# ventilator_circuit.net
KiCad netlist of a schematic drawn in EAGLE
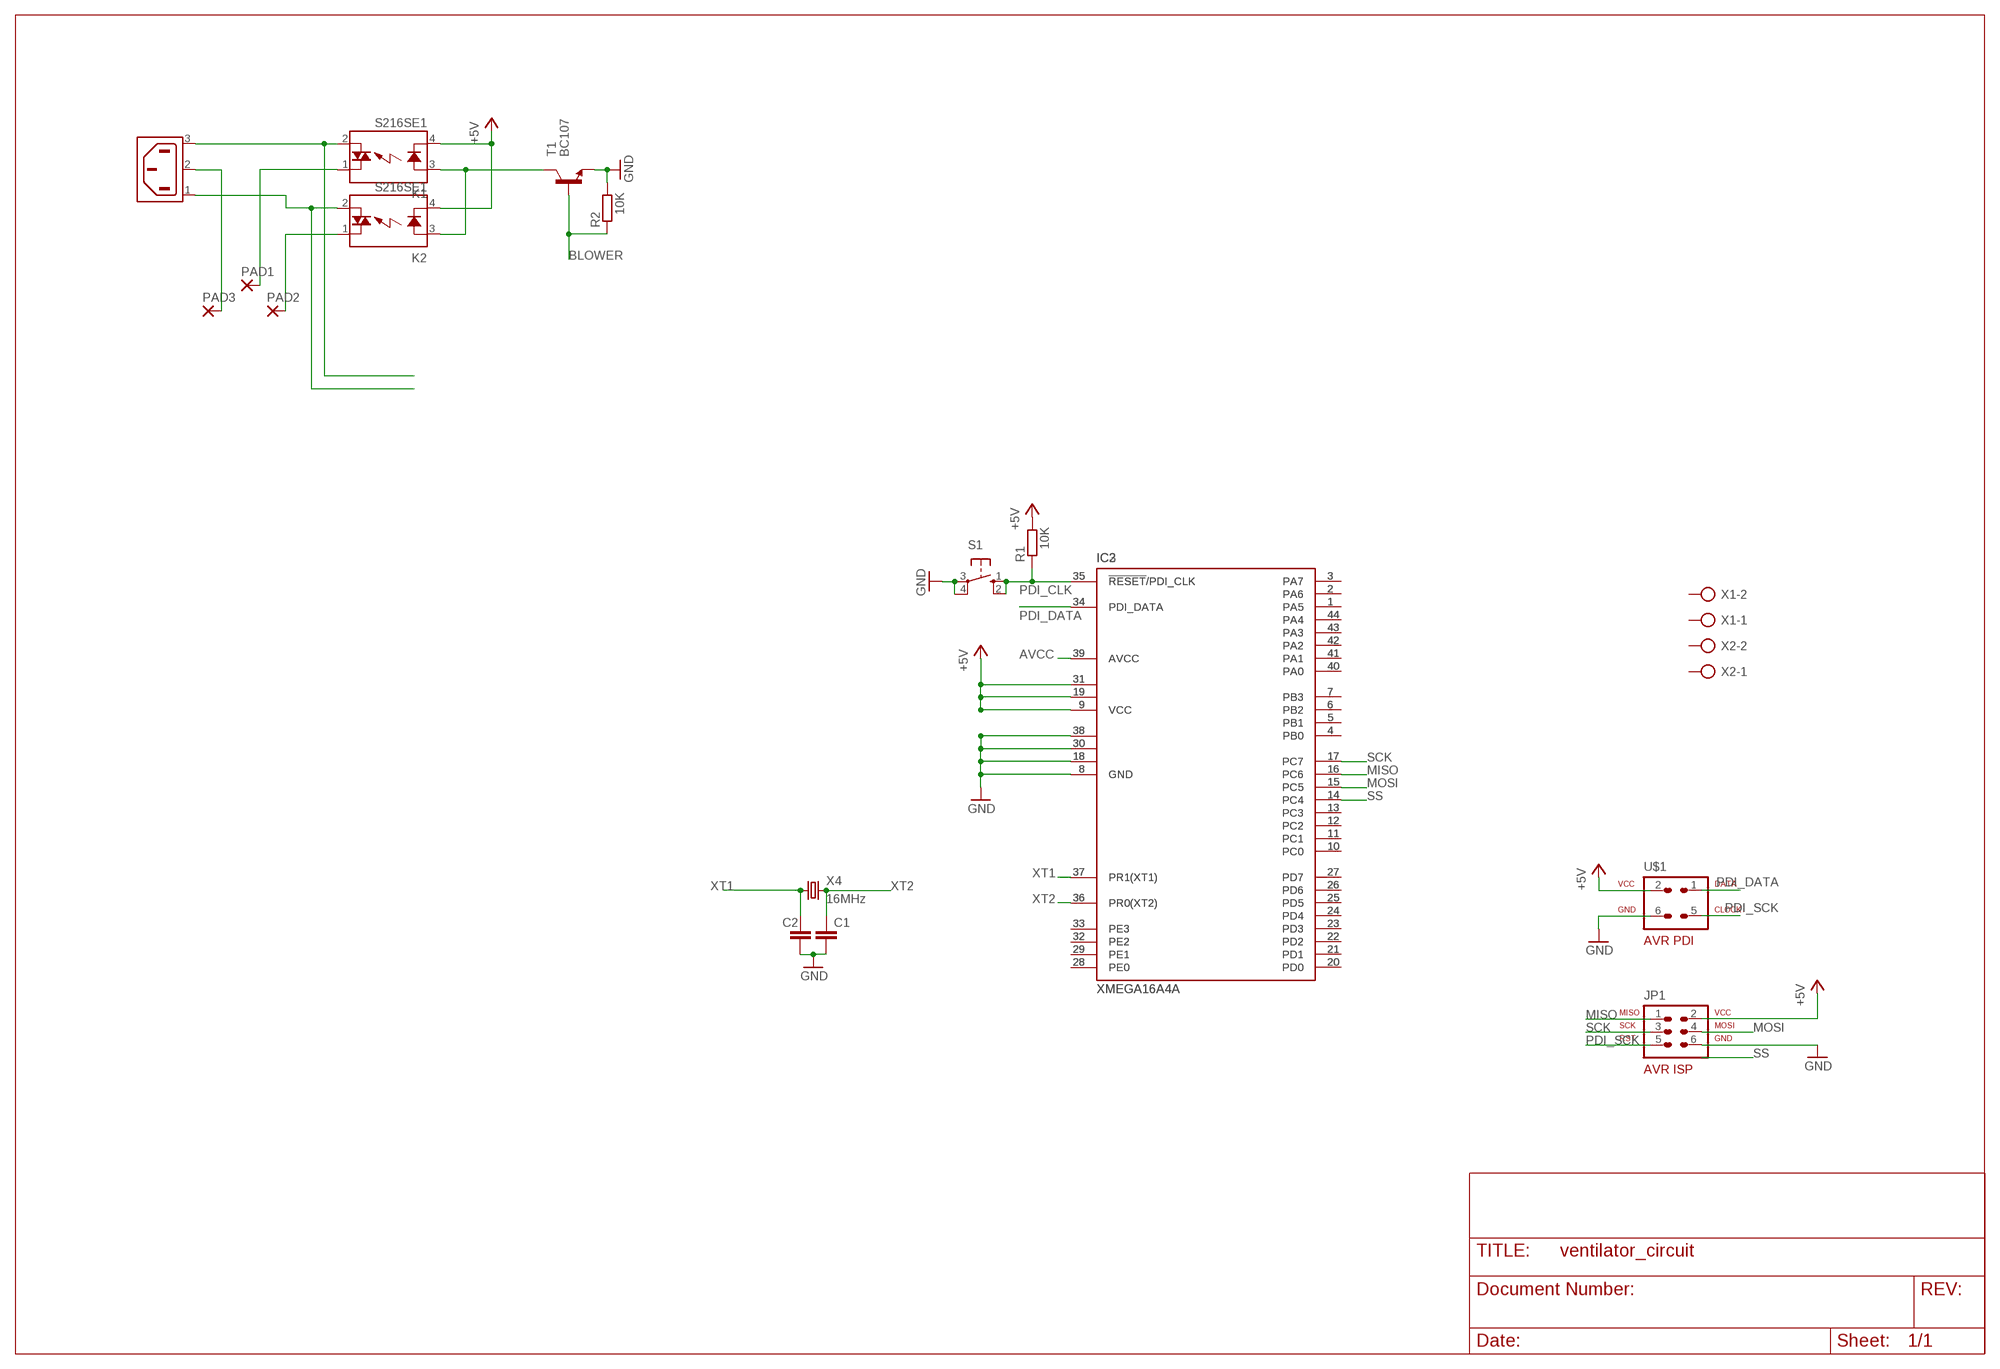
[diagram p0: schematic, sheet 1]

(export (version "E")
  (design (tool "Eeschema 10.0.6"))
  (components
    (comp (ref "C1")
      (value "C-EU025-025X050")
      (footprint "eagle-import:C025-025X050")
      (libsource (lib "eagle-import") (part "C-EU025-025X050"))
    )
    (comp (ref "C2")
      (value "C-EU025-025X050")
      (footprint "eagle-import:C025-025X050")
      (libsource (lib "eagle-import") (part "C-EU025-025X050"))
    )
    (comp (ref "IC2")
      (value "XMEGA16A4A")
      (footprint "eagle-import:TQFP44")
      (libsource (lib "eagle-import") (part "XMEGA16A4A"))
    )
    (comp (ref "IC3")
      (value "XMEGA16A4A")
      (footprint "eagle-import:TQFP44")
      (libsource (lib "eagle-import") (part "XMEGA16A4A"))
    )
    (comp (ref "JP1")
      (value "AVR-ISP-6VERT")
      (footprint "eagle-import:AVR-ISP-6")
      (libsource (lib "eagle-import") (part "AVR-ISP-6VERT"))
    )
    (comp (ref "K1")
      (value "S216SE1")
      (footprint "eagle-import:S2XXEX")
      (libsource (lib "eagle-import") (part "S216SE1"))
    )
    (comp (ref "K2")
      (value "S216SE1")
      (footprint "eagle-import:S2XXEX")
      (libsource (lib "eagle-import") (part "S216SE1"))
    )
    (comp (ref "PAD1")
      (value "3,81/1,4")
      (footprint "eagle-import:3,81_1,4")
      (libsource (lib "eagle-import") (part "3,81/1,4"))
    )
    (comp (ref "PAD2")
      (value "3,81/1,4")
      (footprint "eagle-import:3,81_1,4")
      (libsource (lib "eagle-import") (part "3,81/1,4"))
    )
    (comp (ref "PAD3")
      (value "3,81/1,4")
      (footprint "eagle-import:3,81_1,4")
      (libsource (lib "eagle-import") (part "3,81/1,4"))
    )
    (comp (ref "R1")
      (value "10K")
      (footprint "eagle-import:R0805")
      (libsource (lib "eagle-import") (part "R-EU_R0805"))
    )
    (comp (ref "R2")
      (value "10K")
      (footprint "eagle-import:R0805")
      (libsource (lib "eagle-import") (part "R-EU_R0805"))
    )
    (comp (ref "S1")
      (value "10-XX")
      (footprint "eagle-import:B3F-10XX")
      (fields (field (name "MPN") "B3F-1000"))
      (libsource (lib "eagle-import") (part "10-XX"))
    )
    (comp (ref "T1")
      (value "BC107")
      (footprint "eagle-import:TO18")
      (libsource (lib "eagle-import") (part "BC107"))
    )
    (comp (ref "U$1")
      (value "AVR-PDIVERT")
      (footprint "eagle-import:AVR-ISP-6")
      (libsource (lib "eagle-import") (part "AVR-PDIVERT"))
    )
    (comp (ref "X1")
      (value "AK500/2")
      (footprint "eagle-import:AK500_2")
      (libsource (lib "eagle-import") (part "AK500/2"))
    )
    (comp (ref "X2")
      (value "AK500/2")
      (footprint "eagle-import:AK500_2")
      (libsource (lib "eagle-import") (part "AK500/2"))
    )
    (comp (ref "X3")
      (value "6ESRM-P")
      (footprint "eagle-import:6ESRM-P")
      (fields (field (name "MF") "TYCO ELECTRONICS"))
      (libsource (lib "eagle-import") (part "6ESRM-P"))
    )
    (comp (ref "X4")
      (value "16MHz")
      (footprint "eagle-import:HC49")
      (libsource (lib "eagle-import") (part "CRYSTALS-NOGND-HC49/4H"))
    )
  )
  (nets
    (net (code "1") (name "+5V") (class "Default")
      (node (ref "IC2") (pin "19") (pinfunction "VCC1_19") (pintype "power_in"))
      (node (ref "IC2") (pin "31") (pinfunction "VCC2_31") (pintype "power_in"))
      (node (ref "IC2") (pin "9") (pinfunction "VCC_9") (pintype "power_in"))
      (node (ref "IC3") (pin "19") (pinfunction "VCC1_19") (pintype "power_in"))
      (node (ref "IC3") (pin "31") (pinfunction "VCC2_31") (pintype "power_in"))
      (node (ref "IC3") (pin "9") (pinfunction "VCC_9") (pintype "power_in"))
      (node (ref "JP1") (pin "2") (pinfunction "2_2") (pintype "passive"))
      (node (ref "K1") (pin "4") (pinfunction "K_4") (pintype "passive"))
      (node (ref "K2") (pin "4") (pinfunction "K_4") (pintype "passive"))
      (node (ref "R1") (pin "2") (pinfunction "2_2") (pintype "passive"))
      (node (ref "U$1") (pin "2") (pinfunction "2_2") (pintype "passive"))
    )
    (net (code "2") (name "/AVCC") (class "Default")
      (node (ref "IC2") (pin "39") (pinfunction "AVCC_39") (pintype "power_in"))
      (node (ref "IC3") (pin "39") (pinfunction "AVCC_39") (pintype "power_in"))
    )
    (net (code "3") (name "/BLOWER") (class "Default")
      (node (ref "R2") (pin "1") (pinfunction "1_1") (pintype "passive"))
      (node (ref "T1") (pin "2") (pinfunction "B_2") (pintype "passive"))
    )
    (net (code "4") (name "/MISO") (class "Default")
      (node (ref "IC2") (pin "16") (pinfunction "PC6_16") (pintype "bidirectional"))
      (node (ref "IC3") (pin "16") (pinfunction "PC6_16") (pintype "bidirectional"))
      (node (ref "JP1") (pin "1") (pinfunction "1_1") (pintype "passive"))
    )
    (net (code "5") (name "/MOSI") (class "Default")
      (node (ref "IC2") (pin "15") (pinfunction "PC5_15") (pintype "bidirectional"))
      (node (ref "IC3") (pin "15") (pinfunction "PC5_15") (pintype "bidirectional"))
      (node (ref "JP1") (pin "4") (pinfunction "4_4") (pintype "passive"))
    )
    (net (code "6") (name "/PDI_CLK") (class "Default")
      (node (ref "IC2") (pin "35") (pinfunction "~{RESET}/PDI_CLK_35") (pintype "bidirectional"))
      (node (ref "IC3") (pin "35") (pinfunction "~{RESET}/PDI_CLK_35") (pintype "bidirectional"))
      (node (ref "R1") (pin "1") (pinfunction "1_1") (pintype "passive"))
      (node (ref "S1") (pin "1") (pinfunction "S_1") (pintype "passive"))
      (node (ref "S1") (pin "2") (pinfunction "S1_2") (pintype "passive"))
    )
    (net (code "7") (name "/PDI_DATA") (class "Default")
      (node (ref "IC2") (pin "34") (pinfunction "PDI_DATA_34") (pintype "bidirectional"))
      (node (ref "IC3") (pin "34") (pinfunction "PDI_DATA_34") (pintype "bidirectional"))
      (node (ref "U$1") (pin "1") (pinfunction "1_1") (pintype "passive"))
    )
    (net (code "8") (name "/PDI_SCK") (class "Default")
      (node (ref "JP1") (pin "5") (pinfunction "5_5") (pintype "passive"))
      (node (ref "U$1") (pin "5") (pinfunction "5_5") (pintype "passive"))
    )
    (net (code "9") (name "/SCK") (class "Default")
      (node (ref "IC2") (pin "17") (pinfunction "PC7_17") (pintype "bidirectional"))
      (node (ref "IC3") (pin "17") (pinfunction "PC7_17") (pintype "bidirectional"))
      (node (ref "JP1") (pin "3") (pinfunction "3_3") (pintype "passive"))
    )
    (net (code "10") (name "/SS") (class "Default")
      (node (ref "IC2") (pin "14") (pinfunction "PC4_14") (pintype "bidirectional"))
      (node (ref "IC3") (pin "14") (pinfunction "PC4_14") (pintype "bidirectional"))
    )
    (net (code "11") (name "/XT1") (class "Default")
      (node (ref "C2") (pin "1") (pinfunction "1_1") (pintype "passive"))
      (node (ref "IC2") (pin "37") (pinfunction "PR1(XT1)_37") (pintype "bidirectional"))
      (node (ref "IC3") (pin "37") (pinfunction "PR1(XT1)_37") (pintype "bidirectional"))
      (node (ref "X4") (pin "1") (pinfunction "1_1") (pintype "passive"))
    )
    (net (code "12") (name "/XT2") (class "Default")
      (node (ref "C1") (pin "1") (pinfunction "1_1") (pintype "passive"))
      (node (ref "IC2") (pin "36") (pinfunction "PR0(XT2)_36") (pintype "bidirectional"))
      (node (ref "IC3") (pin "36") (pinfunction "PR0(XT2)_36") (pintype "bidirectional"))
      (node (ref "X4") (pin "2") (pinfunction "2_2") (pintype "passive"))
    )
    (net (code "13") (name "GND") (class "Default")
      (node (ref "C1") (pin "2") (pinfunction "2_2") (pintype "passive"))
      (node (ref "C2") (pin "2") (pinfunction "2_2") (pintype "passive"))
      (node (ref "IC2") (pin "18") (pinfunction "GND1_18") (pintype "power_in"))
      (node (ref "IC2") (pin "30") (pinfunction "GND2_30") (pintype "power_in"))
      (node (ref "IC2") (pin "38") (pinfunction "GND3_38") (pintype "power_in"))
      (node (ref "IC2") (pin "8") (pinfunction "GND_8") (pintype "power_in"))
      (node (ref "IC3") (pin "18") (pinfunction "GND1_18") (pintype "power_in"))
      (node (ref "IC3") (pin "30") (pinfunction "GND2_30") (pintype "power_in"))
      (node (ref "IC3") (pin "38") (pinfunction "GND3_38") (pintype "power_in"))
      (node (ref "IC3") (pin "8") (pinfunction "GND_8") (pintype "power_in"))
      (node (ref "JP1") (pin "6") (pinfunction "6_6") (pintype "passive"))
      (node (ref "R2") (pin "2") (pinfunction "2_2") (pintype "passive"))
      (node (ref "S1") (pin "3") (pinfunction "P_3") (pintype "passive"))
      (node (ref "S1") (pin "4") (pinfunction "P1_4") (pintype "passive"))
      (node (ref "T1") (pin "1") (pinfunction "E_1") (pintype "passive"))
      (node (ref "U$1") (pin "6") (pinfunction "6_6") (pintype "passive"))
    )
    (net (code "14") (name "Net-(IC2-PA0)") (class "Default")
      (node (ref "IC2") (pin "40") (pinfunction "PA0_40") (pintype "bidirectional"))
      (node (ref "IC3") (pin "40") (pinfunction "PA0_40") (pintype "bidirectional"))
    )
    (net (code "15") (name "Net-(IC2-PA1)") (class "Default")
      (node (ref "IC2") (pin "41") (pinfunction "PA1_41") (pintype "bidirectional"))
      (node (ref "IC3") (pin "41") (pinfunction "PA1_41") (pintype "bidirectional"))
    )
    (net (code "16") (name "Net-(IC2-PA2)") (class "Default")
      (node (ref "IC2") (pin "42") (pinfunction "PA2_42") (pintype "bidirectional"))
      (node (ref "IC3") (pin "42") (pinfunction "PA2_42") (pintype "bidirectional"))
    )
    (net (code "17") (name "Net-(IC2-PA3)") (class "Default")
      (node (ref "IC2") (pin "43") (pinfunction "PA3_43") (pintype "bidirectional"))
      (node (ref "IC3") (pin "43") (pinfunction "PA3_43") (pintype "bidirectional"))
    )
    (net (code "18") (name "Net-(IC2-PA4)") (class "Default")
      (node (ref "IC2") (pin "44") (pinfunction "PA4_44") (pintype "bidirectional"))
      (node (ref "IC3") (pin "44") (pinfunction "PA4_44") (pintype "bidirectional"))
    )
    (net (code "19") (name "Net-(IC2-PA5)") (class "Default")
      (node (ref "IC2") (pin "1") (pinfunction "PA5_1") (pintype "bidirectional"))
      (node (ref "IC3") (pin "1") (pinfunction "PA5_1") (pintype "bidirectional"))
    )
    (net (code "20") (name "Net-(IC2-PA6)") (class "Default")
      (node (ref "IC2") (pin "2") (pinfunction "PA6_2") (pintype "bidirectional"))
      (node (ref "IC3") (pin "2") (pinfunction "PA6_2") (pintype "bidirectional"))
    )
    (net (code "21") (name "Net-(IC2-PA7)") (class "Default")
      (node (ref "IC2") (pin "3") (pinfunction "PA7_3") (pintype "bidirectional"))
      (node (ref "IC3") (pin "3") (pinfunction "PA7_3") (pintype "bidirectional"))
    )
    (net (code "22") (name "Net-(IC2-PB0)") (class "Default")
      (node (ref "IC2") (pin "4") (pinfunction "PB0_4") (pintype "bidirectional"))
      (node (ref "IC3") (pin "4") (pinfunction "PB0_4") (pintype "bidirectional"))
    )
    (net (code "23") (name "Net-(IC2-PB1)") (class "Default")
      (node (ref "IC2") (pin "5") (pinfunction "PB1_5") (pintype "bidirectional"))
      (node (ref "IC3") (pin "5") (pinfunction "PB1_5") (pintype "bidirectional"))
    )
    (net (code "24") (name "Net-(IC2-PB2)") (class "Default")
      (node (ref "IC2") (pin "6") (pinfunction "PB2_6") (pintype "bidirectional"))
      (node (ref "IC3") (pin "6") (pinfunction "PB2_6") (pintype "bidirectional"))
    )
    (net (code "25") (name "Net-(IC2-PB3)") (class "Default")
      (node (ref "IC2") (pin "7") (pinfunction "PB3_7") (pintype "bidirectional"))
      (node (ref "IC3") (pin "7") (pinfunction "PB3_7") (pintype "bidirectional"))
    )
    (net (code "26") (name "Net-(IC2-PC0)") (class "Default")
      (node (ref "IC2") (pin "10") (pinfunction "PC0_10") (pintype "bidirectional"))
      (node (ref "IC3") (pin "10") (pinfunction "PC0_10") (pintype "bidirectional"))
    )
    (net (code "27") (name "Net-(IC2-PC1)") (class "Default")
      (node (ref "IC2") (pin "11") (pinfunction "PC1_11") (pintype "bidirectional"))
      (node (ref "IC3") (pin "11") (pinfunction "PC1_11") (pintype "bidirectional"))
    )
    (net (code "28") (name "Net-(IC2-PC2)") (class "Default")
      (node (ref "IC2") (pin "12") (pinfunction "PC2_12") (pintype "bidirectional"))
      (node (ref "IC3") (pin "12") (pinfunction "PC2_12") (pintype "bidirectional"))
    )
    (net (code "29") (name "Net-(IC2-PC3)") (class "Default")
      (node (ref "IC2") (pin "13") (pinfunction "PC3_13") (pintype "bidirectional"))
      (node (ref "IC3") (pin "13") (pinfunction "PC3_13") (pintype "bidirectional"))
    )
    (net (code "30") (name "Net-(IC2-PD0)") (class "Default")
      (node (ref "IC2") (pin "20") (pinfunction "PD0_20") (pintype "bidirectional"))
      (node (ref "IC3") (pin "20") (pinfunction "PD0_20") (pintype "bidirectional"))
    )
    (net (code "31") (name "Net-(IC2-PD1)") (class "Default")
      (node (ref "IC2") (pin "21") (pinfunction "PD1_21") (pintype "bidirectional"))
      (node (ref "IC3") (pin "21") (pinfunction "PD1_21") (pintype "bidirectional"))
    )
    (net (code "32") (name "Net-(IC2-PD2)") (class "Default")
      (node (ref "IC2") (pin "22") (pinfunction "PD2_22") (pintype "bidirectional"))
      (node (ref "IC3") (pin "22") (pinfunction "PD2_22") (pintype "bidirectional"))
    )
    (net (code "33") (name "Net-(IC2-PD3)") (class "Default")
      (node (ref "IC2") (pin "23") (pinfunction "PD3_23") (pintype "bidirectional"))
      (node (ref "IC3") (pin "23") (pinfunction "PD3_23") (pintype "bidirectional"))
    )
    (net (code "34") (name "Net-(IC2-PD4)") (class "Default")
      (node (ref "IC2") (pin "24") (pinfunction "PD4_24") (pintype "bidirectional"))
      (node (ref "IC3") (pin "24") (pinfunction "PD4_24") (pintype "bidirectional"))
    )
    (net (code "35") (name "Net-(IC2-PD5)") (class "Default")
      (node (ref "IC2") (pin "25") (pinfunction "PD5_25") (pintype "bidirectional"))
      (node (ref "IC3") (pin "25") (pinfunction "PD5_25") (pintype "bidirectional"))
    )
    (net (code "36") (name "Net-(IC2-PD6)") (class "Default")
      (node (ref "IC2") (pin "26") (pinfunction "PD6_26") (pintype "bidirectional"))
      (node (ref "IC3") (pin "26") (pinfunction "PD6_26") (pintype "bidirectional"))
    )
    (net (code "37") (name "Net-(IC2-PD7)") (class "Default")
      (node (ref "IC2") (pin "27") (pinfunction "PD7_27") (pintype "bidirectional"))
      (node (ref "IC3") (pin "27") (pinfunction "PD7_27") (pintype "bidirectional"))
    )
    (net (code "38") (name "Net-(IC2-PE0)") (class "Default")
      (node (ref "IC2") (pin "28") (pinfunction "PE0_28") (pintype "bidirectional"))
      (node (ref "IC3") (pin "28") (pinfunction "PE0_28") (pintype "bidirectional"))
    )
    (net (code "39") (name "Net-(IC2-PE1)") (class "Default")
      (node (ref "IC2") (pin "29") (pinfunction "PE1_29") (pintype "bidirectional"))
      (node (ref "IC3") (pin "29") (pinfunction "PE1_29") (pintype "bidirectional"))
    )
    (net (code "40") (name "Net-(IC2-PE2)") (class "Default")
      (node (ref "IC2") (pin "32") (pinfunction "PE2_32") (pintype "bidirectional"))
      (node (ref "IC3") (pin "32") (pinfunction "PE2_32") (pintype "bidirectional"))
    )
    (net (code "41") (name "Net-(IC2-PE3)") (class "Default")
      (node (ref "IC2") (pin "33") (pinfunction "PE3_33") (pintype "bidirectional"))
      (node (ref "IC3") (pin "33") (pinfunction "PE3_33") (pintype "bidirectional"))
    )
    (net (code "42") (name "Net-(K1-A)") (class "Default")
      (node (ref "K1") (pin "3") (pinfunction "A_3") (pintype "passive"))
      (node (ref "K2") (pin "3") (pinfunction "A_3") (pintype "passive"))
      (node (ref "T1") (pin "3") (pinfunction "C_3") (pintype "passive"))
    )
    (net (code "43") (name "Net-(K1-DS1)") (class "Default")
      (node (ref "K1") (pin "1") (pinfunction "DS1_1") (pintype "passive"))
      (node (ref "PAD1") (pin "1") (pinfunction "P_1") (pintype "passive"))
    )
    (net (code "44") (name "Net-(K1-DS2)") (class "Default")
      (node (ref "K1") (pin "2") (pinfunction "DS2_2") (pintype "passive"))
      (node (ref "X3") (pin "3") (pinfunction "AC2_3") (pintype "passive"))
    )
    (net (code "45") (name "Net-(K2-DS1)") (class "Default")
      (node (ref "K2") (pin "1") (pinfunction "DS1_1") (pintype "passive"))
      (node (ref "PAD2") (pin "1") (pinfunction "P_1") (pintype "passive"))
    )
    (net (code "46") (name "Net-(K2-DS2)") (class "Default")
      (node (ref "K2") (pin "2") (pinfunction "DS2_2") (pintype "passive"))
      (node (ref "X3") (pin "1") (pinfunction "AC1_1") (pintype "passive"))
    )
    (net (code "47") (name "Net-(PAD3-P)") (class "Default")
      (node (ref "PAD3") (pin "1") (pinfunction "P_1") (pintype "passive"))
      (node (ref "X3") (pin "2") (pinfunction "SH_2") (pintype "passive"))
    )
    (net (code "48") (name "unconnected-(X1A-KL-Pad1)") (class "Default")
      (node (ref "X1") (pin "1") (pinfunction "KL_1") (pintype "passive"))
    )
    (net (code "49") (name "unconnected-(X1B-KL-Pad2)") (class "Default")
      (node (ref "X1") (pin "2") (pinfunction "KL_2") (pintype "passive"))
    )
    (net (code "50") (name "unconnected-(X2A-KL-Pad1)") (class "Default")
      (node (ref "X2") (pin "1") (pinfunction "KL_1") (pintype "passive"))
    )
    (net (code "51") (name "unconnected-(X2B-KL-Pad2)") (class "Default")
      (node (ref "X2") (pin "2") (pinfunction "KL_2") (pintype "passive"))
    )
  )
)
